# fnir_motherboard.net
KiCad netlist of a schematic drawn in EAGLE
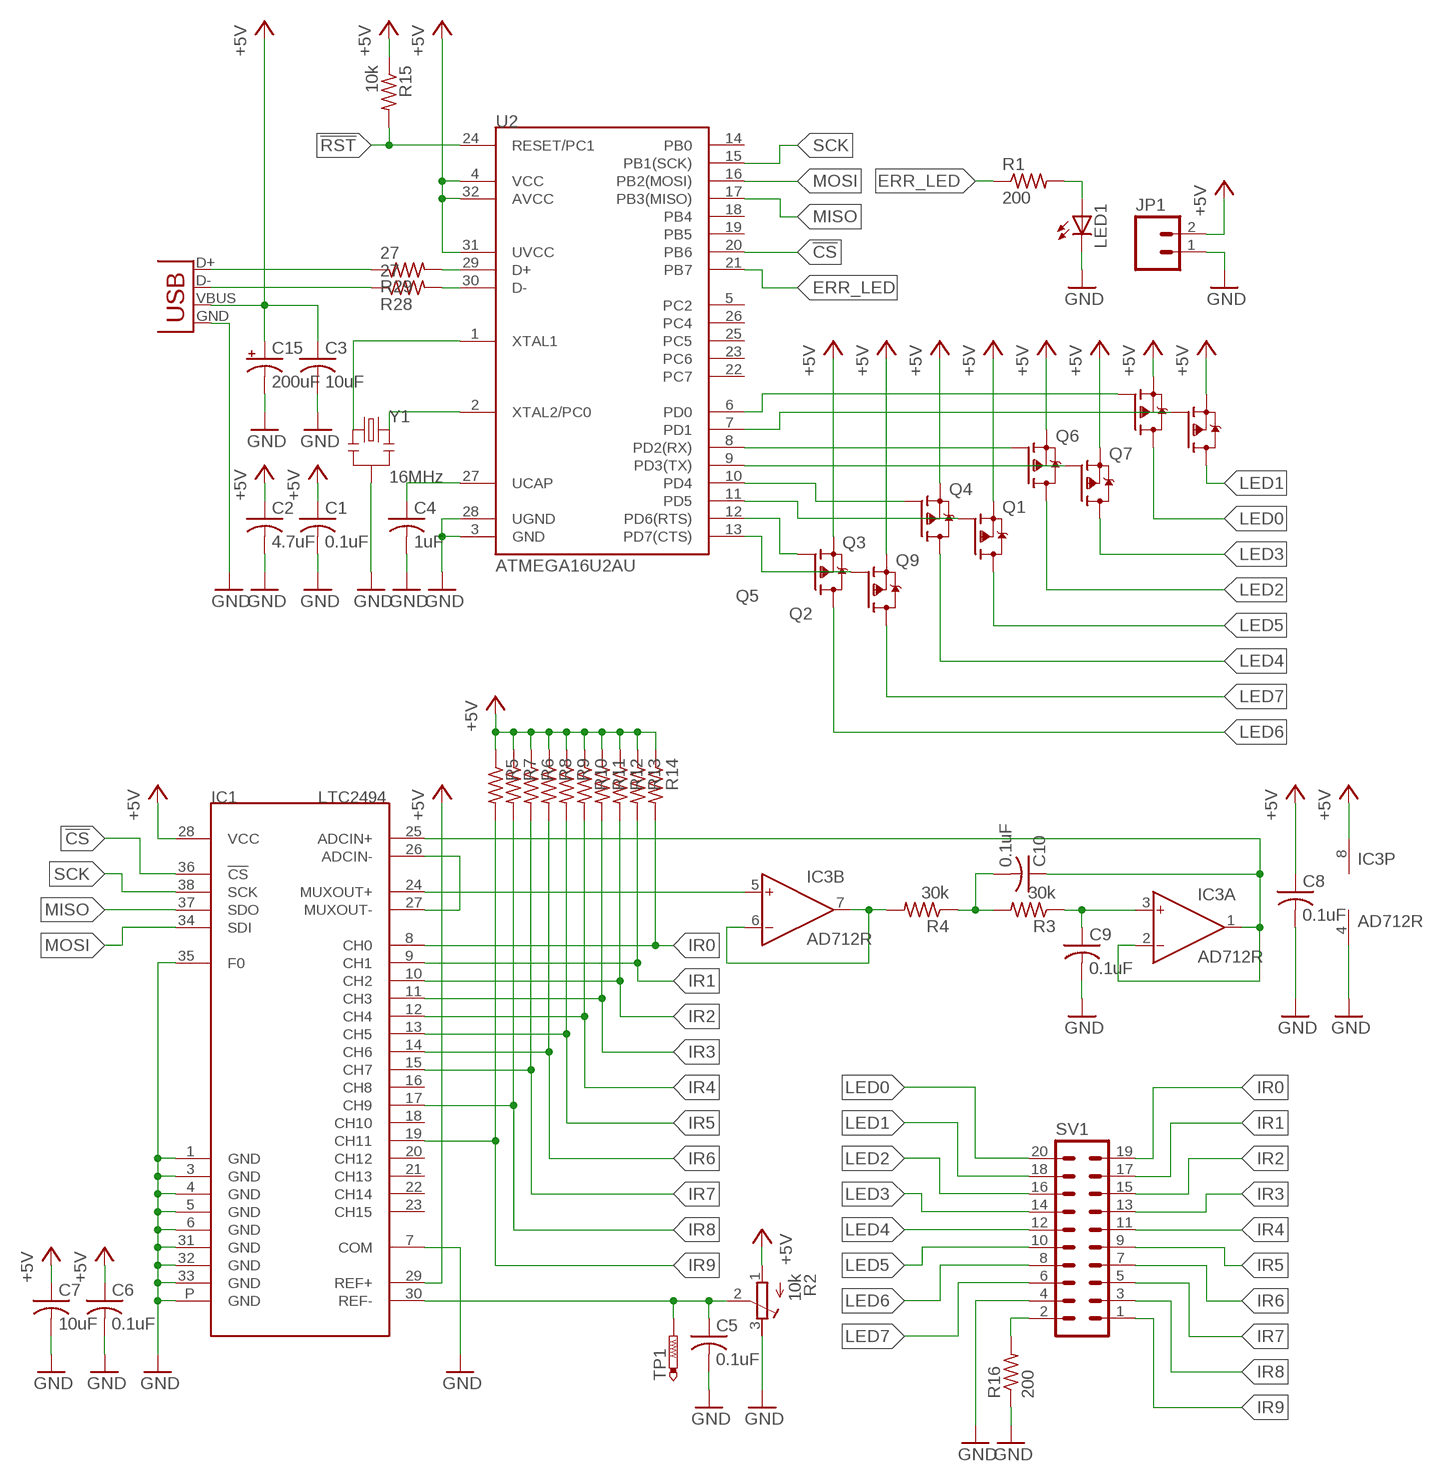
[diagram p0: schematic, sheet 1]

(export (version "E")
  (design (tool "Eeschema 10.0.6"))
  (components
    (comp (ref "C1")
      (value "0.1uF")
      (footprint "eagle-import:C1206")
      (libsource (lib "eagle-import") (part "C-USC1206"))
    )
    (comp (ref "C2")
      (value "4.7uF")
      (footprint "eagle-import:C1206")
      (libsource (lib "eagle-import") (part "C-USC1206"))
    )
    (comp (ref "C3")
      (value "10uF")
      (footprint "eagle-import:C1206")
      (libsource (lib "eagle-import") (part "C-USC1206"))
    )
    (comp (ref "C4")
      (value "1uF")
      (footprint "eagle-import:C1206")
      (libsource (lib "eagle-import") (part "C-USC1206"))
    )
    (comp (ref "C5")
      (value "0.1uF")
      (footprint "eagle-import:C1206")
      (libsource (lib "eagle-import") (part "C-USC1206"))
    )
    (comp (ref "C6")
      (value "0.1uF")
      (footprint "eagle-import:C1206")
      (libsource (lib "eagle-import") (part "C-USC1206"))
    )
    (comp (ref "C7")
      (value "10uF")
      (footprint "eagle-import:C1206")
      (libsource (lib "eagle-import") (part "C-USC1206"))
    )
    (comp (ref "C8")
      (value "0.1uF")
      (footprint "eagle-import:C1206")
      (libsource (lib "eagle-import") (part "C-USC1206"))
    )
    (comp (ref "C9")
      (value "0.1uF")
      (footprint "eagle-import:C1206")
      (libsource (lib "eagle-import") (part "C-USC1206"))
    )
    (comp (ref "C10")
      (value "0.1uF")
      (footprint "eagle-import:C1206")
      (libsource (lib "eagle-import") (part "C-USC1206"))
    )
    (comp (ref "C15")
      (value "200uF")
      (footprint "eagle-import:PANASONIC_D")
      (libsource (lib "eagle-import") (part "CPOL-USD"))
    )
    (comp (ref "IC1")
      (value "LTC2494")
      (footprint "eagle-import:QFN38-7X12")
      (libsource (lib "eagle-import") (part "LTC2494"))
    )
    (comp (ref "IC3")
      (value "AD712R")
      (footprint "eagle-import:SO8")
      (fields (field (name "MF") "ALTERA CORPORATION") (field (name "MPN") "AD712KRZ"))
      (libsource (lib "eagle-import") (part "AD712R"))
    )
    (comp (ref "JP1")
      (value "M02PTH")
      (footprint "eagle-import:1X02")
      (libsource (lib "eagle-import") (part "M02PTH"))
    )
    (comp (ref "LED1")
      (value "LEDCHIPLED_1206")
      (footprint "eagle-import:CHIPLED_1206")
      (libsource (lib "eagle-import") (part "LEDCHIPLED_1206"))
    )
    (comp (ref "Q1")
      (value "TRANSISTOR_FET_TSM2301CX")
      (footprint "eagle-import:SOT-23")
      (libsource (lib "eagle-import") (part "TRANSISTOR_FET_TSM2301CX"))
    )
    (comp (ref "Q2")
      (value "TRANSISTOR_FET_TSM2301CX")
      (footprint "eagle-import:SOT-23")
      (libsource (lib "eagle-import") (part "TRANSISTOR_FET_TSM2301CX"))
    )
    (comp (ref "Q3")
      (value "TRANSISTOR_FET_TSM2301CX")
      (footprint "eagle-import:SOT-23")
      (libsource (lib "eagle-import") (part "TRANSISTOR_FET_TSM2301CX"))
    )
    (comp (ref "Q4")
      (value "TRANSISTOR_FET_TSM2301CX")
      (footprint "eagle-import:SOT-23")
      (libsource (lib "eagle-import") (part "TRANSISTOR_FET_TSM2301CX"))
    )
    (comp (ref "Q5")
      (value "TRANSISTOR_FET_TSM2301CX")
      (footprint "eagle-import:SOT-23")
      (libsource (lib "eagle-import") (part "TRANSISTOR_FET_TSM2301CX"))
    )
    (comp (ref "Q6")
      (value "TRANSISTOR_FET_TSM2301CX")
      (footprint "eagle-import:SOT-23")
      (libsource (lib "eagle-import") (part "TRANSISTOR_FET_TSM2301CX"))
    )
    (comp (ref "Q7")
      (value "TRANSISTOR_FET_TSM2301CX")
      (footprint "eagle-import:SOT-23")
      (libsource (lib "eagle-import") (part "TRANSISTOR_FET_TSM2301CX"))
    )
    (comp (ref "Q9")
      (value "TRANSISTOR_FET_TSM2301CX")
      (footprint "eagle-import:SOT-23")
      (libsource (lib "eagle-import") (part "TRANSISTOR_FET_TSM2301CX"))
    )
    (comp (ref "R1")
      (value "200")
      (footprint "eagle-import:R1206")
      (libsource (lib "eagle-import") (part "R-US_R1206"))
    )
    (comp (ref "R2")
      (value "10k")
      (footprint "eagle-import:RTRIM3304W")
      (libsource (lib "eagle-import") (part "R-TRIMM3304W"))
    )
    (comp (ref "R3")
      (value "30k")
      (footprint "eagle-import:R1206")
      (libsource (lib "eagle-import") (part "R-US_R1206"))
    )
    (comp (ref "R4")
      (value "30k")
      (footprint "eagle-import:R1206")
      (libsource (lib "eagle-import") (part "R-US_R1206"))
    )
    (comp (ref "R5")
      (value "R-US_R1206")
      (footprint "eagle-import:R1206")
      (libsource (lib "eagle-import") (part "R-US_R1206"))
    )
    (comp (ref "R6")
      (value "R-US_R1206")
      (footprint "eagle-import:R1206")
      (libsource (lib "eagle-import") (part "R-US_R1206"))
    )
    (comp (ref "R7")
      (value "R-US_R1206")
      (footprint "eagle-import:R1206")
      (libsource (lib "eagle-import") (part "R-US_R1206"))
    )
    (comp (ref "R8")
      (value "R-US_R1206")
      (footprint "eagle-import:R1206")
      (libsource (lib "eagle-import") (part "R-US_R1206"))
    )
    (comp (ref "R9")
      (value "R-US_R1206")
      (footprint "eagle-import:R1206")
      (libsource (lib "eagle-import") (part "R-US_R1206"))
    )
    (comp (ref "R10")
      (value "R-US_R1206")
      (footprint "eagle-import:R1206")
      (libsource (lib "eagle-import") (part "R-US_R1206"))
    )
    (comp (ref "R11")
      (value "R-US_R1206")
      (footprint "eagle-import:R1206")
      (libsource (lib "eagle-import") (part "R-US_R1206"))
    )
    (comp (ref "R12")
      (value "R-US_R1206")
      (footprint "eagle-import:R1206")
      (libsource (lib "eagle-import") (part "R-US_R1206"))
    )
    (comp (ref "R13")
      (value "R-US_R1206")
      (footprint "eagle-import:R1206")
      (libsource (lib "eagle-import") (part "R-US_R1206"))
    )
    (comp (ref "R14")
      (value "R-US_R1206")
      (footprint "eagle-import:R1206")
      (libsource (lib "eagle-import") (part "R-US_R1206"))
    )
    (comp (ref "R15")
      (value "10k")
      (footprint "eagle-import:R1206")
      (libsource (lib "eagle-import") (part "R-US_R1206"))
    )
    (comp (ref "R16")
      (value "200")
      (footprint "eagle-import:R1206")
      (libsource (lib "eagle-import") (part "R-US_R1206"))
    )
    (comp (ref "R28")
      (value "27")
      (footprint "eagle-import:R1206")
      (libsource (lib "eagle-import") (part "R-US_R1206"))
    )
    (comp (ref "R29")
      (value "27")
      (footprint "eagle-import:R1206")
      (libsource (lib "eagle-import") (part "R-US_R1206"))
    )
    (comp (ref "SV1")
      (value "MA10-2")
      (footprint "eagle-import:MA10-2")
      (libsource (lib "eagle-import") (part "MA10-2"))
    )
    (comp (ref "TP1")
      (value "PTR1B1,27")
      (footprint "eagle-import:B1,27")
      (libsource (lib "eagle-import") (part "PTR1B1,27"))
    )
    (comp (ref "U2")
      (value "ATMEGA16U2AU")
      (footprint "eagle-import:TQFP32-08")
      (libsource (lib "eagle-import") (part "ATMEGA8U2AU"))
    )
    (comp (ref "X2")
      (value "USB-SMD-NS")
      (footprint "eagle-import:USB-MINIB-NOSTOP")
      (libsource (lib "eagle-import") (part "USB-SMD-NS"))
    )
    (comp (ref "Y1")
      (value "16MHz")
      (footprint "eagle-import:RESONATOR-SMD")
      (libsource (lib "eagle-import") (part "RESONATORSMD"))
    )
  )
  (nets
    (net (code "1") (name "+5V") (class "Default")
      (node (ref "C1") (pin "1") (pinfunction "1_1") (pintype "passive"))
      (node (ref "C15") (pin "+") (pinfunction "+_+") (pintype "passive"))
      (node (ref "C2") (pin "1") (pinfunction "1_1") (pintype "passive"))
      (node (ref "C3") (pin "1") (pinfunction "1_1") (pintype "passive"))
      (node (ref "C6") (pin "1") (pinfunction "1_1") (pintype "passive"))
      (node (ref "C7") (pin "1") (pinfunction "1_1") (pintype "passive"))
      (node (ref "C8") (pin "1") (pinfunction "1_1") (pintype "passive"))
      (node (ref "IC1") (pin "28") (pinfunction "VCC_28") (pintype "bidirectional"))
      (node (ref "IC1") (pin "29") (pinfunction "REF+_29") (pintype "bidirectional"))
      (node (ref "IC3") (pin "8") (pinfunction "V+_8") (pintype "power_in"))
      (node (ref "JP1") (pin "2") (pinfunction "2_2") (pintype "passive"))
      (node (ref "Q1") (pin "2") (pinfunction "S_2") (pintype "passive"))
      (node (ref "Q2") (pin "2") (pinfunction "S_2") (pintype "passive"))
      (node (ref "Q3") (pin "2") (pinfunction "S_2") (pintype "passive"))
      (node (ref "Q4") (pin "2") (pinfunction "S_2") (pintype "passive"))
      (node (ref "Q5") (pin "2") (pinfunction "S_2") (pintype "passive"))
      (node (ref "Q6") (pin "2") (pinfunction "S_2") (pintype "passive"))
      (node (ref "Q7") (pin "2") (pinfunction "S_2") (pintype "passive"))
      (node (ref "Q9") (pin "2") (pinfunction "S_2") (pintype "passive"))
      (node (ref "R10") (pin "1") (pinfunction "1_1") (pintype "passive"))
      (node (ref "R11") (pin "1") (pinfunction "1_1") (pintype "passive"))
      (node (ref "R12") (pin "1") (pinfunction "1_1") (pintype "passive"))
      (node (ref "R13") (pin "1") (pinfunction "1_1") (pintype "passive"))
      (node (ref "R14") (pin "1") (pinfunction "1_1") (pintype "passive"))
      (node (ref "R15") (pin "1") (pinfunction "1_1") (pintype "passive"))
      (node (ref "R2") (pin "1") (pinfunction "A_1") (pintype "passive"))
      (node (ref "R5") (pin "1") (pinfunction "1_1") (pintype "passive"))
      (node (ref "R6") (pin "1") (pinfunction "1_1") (pintype "passive"))
      (node (ref "R7") (pin "1") (pinfunction "1_1") (pintype "passive"))
      (node (ref "R8") (pin "1") (pinfunction "1_1") (pintype "passive"))
      (node (ref "R9") (pin "1") (pinfunction "1_1") (pintype "passive"))
      (node (ref "U2") (pin "31") (pinfunction "UVCC_31") (pintype "bidirectional"))
      (node (ref "U2") (pin "32") (pinfunction "AVCC_32") (pintype "bidirectional"))
      (node (ref "U2") (pin "4") (pinfunction "VCC_4") (pintype "bidirectional"))
      (node (ref "X2") (pin "VBUS") (pinfunction "VBUS_VBUS") (pintype "bidirectional"))
    )
    (net (code "2") (name "/~{CS}") (class "Default")
      (node (ref "IC1") (pin "36") (pinfunction "~{CS}_36") (pintype "bidirectional"))
      (node (ref "U2") (pin "20") (pinfunction "PB6_20") (pintype "bidirectional"))
    )
    (net (code "3") (name "/~{RST}") (class "Default")
      (node (ref "R15") (pin "2") (pinfunction "2_2") (pintype "passive"))
      (node (ref "U2") (pin "24") (pinfunction "RESET/PC1_24") (pintype "bidirectional"))
    )
    (net (code "4") (name "ERR_LED") (class "Default")
      (node (ref "R1") (pin "1") (pinfunction "1_1") (pintype "passive"))
      (node (ref "U2") (pin "21") (pinfunction "PB7_21") (pintype "bidirectional"))
    )
    (net (code "5") (name "GND") (class "Default")
      (node (ref "C1") (pin "2") (pinfunction "2_2") (pintype "passive"))
      (node (ref "C15") (pin "-") (pinfunction "-_-") (pintype "passive"))
      (node (ref "C2") (pin "2") (pinfunction "2_2") (pintype "passive"))
      (node (ref "C3") (pin "2") (pinfunction "2_2") (pintype "passive"))
      (node (ref "C4") (pin "2") (pinfunction "2_2") (pintype "passive"))
      (node (ref "C5") (pin "2") (pinfunction "2_2") (pintype "passive"))
      (node (ref "C6") (pin "2") (pinfunction "2_2") (pintype "passive"))
      (node (ref "C7") (pin "2") (pinfunction "2_2") (pintype "passive"))
      (node (ref "C8") (pin "2") (pinfunction "2_2") (pintype "passive"))
      (node (ref "C9") (pin "2") (pinfunction "2_2") (pintype "passive"))
      (node (ref "IC1") (pin "1") (pinfunction "GND_1") (pintype "bidirectional"))
      (node (ref "IC1") (pin "3") (pinfunction "GND_3") (pintype "bidirectional"))
      (node (ref "IC1") (pin "31") (pinfunction "GND_31") (pintype "bidirectional"))
      (node (ref "IC1") (pin "32") (pinfunction "GND_32") (pintype "bidirectional"))
      (node (ref "IC1") (pin "33") (pinfunction "GND_33") (pintype "bidirectional"))
      (node (ref "IC1") (pin "35") (pinfunction "F0_35") (pintype "bidirectional"))
      (node (ref "IC1") (pin "4") (pinfunction "GND_4") (pintype "bidirectional"))
      (node (ref "IC1") (pin "5") (pinfunction "GND_5") (pintype "bidirectional"))
      (node (ref "IC1") (pin "6") (pinfunction "GND_6") (pintype "bidirectional"))
      (node (ref "IC1") (pin "7") (pinfunction "COM_7") (pintype "bidirectional"))
      (node (ref "IC1") (pin "P") (pinfunction "GND_P") (pintype "bidirectional"))
      (node (ref "IC3") (pin "4") (pinfunction "V-_4") (pintype "power_in"))
      (node (ref "JP1") (pin "1") (pinfunction "1_1") (pintype "passive"))
      (node (ref "LED1") (pin "C") (pinfunction "C_C") (pintype "passive"))
      (node (ref "R16") (pin "1") (pinfunction "1_1") (pintype "passive"))
      (node (ref "R2") (pin "3") (pinfunction "E_3") (pintype "passive"))
      (node (ref "SV1") (pin "4") (pinfunction "4_4") (pintype "passive"))
      (node (ref "U2") (pin "28") (pinfunction "UGND_28") (pintype "bidirectional"))
      (node (ref "U2") (pin "3") (pinfunction "GND_3") (pintype "bidirectional"))
      (node (ref "X2") (pin "GND") (pinfunction "GND_GND") (pintype "bidirectional"))
      (node (ref "Y1") (pin "2") (pinfunction "2_2") (pintype "passive"))
    )
    (net (code "6") (name "IR0") (class "Default")
      (node (ref "IC1") (pin "8") (pinfunction "CH0_8") (pintype "bidirectional"))
      (node (ref "R14") (pin "2") (pinfunction "2_2") (pintype "passive"))
      (node (ref "SV1") (pin "19") (pinfunction "19_19") (pintype "passive"))
    )
    (net (code "7") (name "IR1") (class "Default")
      (node (ref "IC1") (pin "9") (pinfunction "CH1_9") (pintype "bidirectional"))
      (node (ref "R13") (pin "2") (pinfunction "2_2") (pintype "passive"))
      (node (ref "SV1") (pin "17") (pinfunction "17_17") (pintype "passive"))
    )
    (net (code "8") (name "IR2") (class "Default")
      (node (ref "IC1") (pin "10") (pinfunction "CH2_10") (pintype "bidirectional"))
      (node (ref "R12") (pin "2") (pinfunction "2_2") (pintype "passive"))
      (node (ref "SV1") (pin "15") (pinfunction "15_15") (pintype "passive"))
    )
    (net (code "9") (name "IR3") (class "Default")
      (node (ref "IC1") (pin "11") (pinfunction "CH3_11") (pintype "bidirectional"))
      (node (ref "R11") (pin "2") (pinfunction "2_2") (pintype "passive"))
      (node (ref "SV1") (pin "13") (pinfunction "13_13") (pintype "passive"))
    )
    (net (code "10") (name "IR4") (class "Default")
      (node (ref "IC1") (pin "12") (pinfunction "CH4_12") (pintype "bidirectional"))
      (node (ref "R10") (pin "2") (pinfunction "2_2") (pintype "passive"))
      (node (ref "SV1") (pin "11") (pinfunction "11_11") (pintype "passive"))
    )
    (net (code "11") (name "IR5") (class "Default")
      (node (ref "IC1") (pin "13") (pinfunction "CH5_13") (pintype "bidirectional"))
      (node (ref "R9") (pin "2") (pinfunction "2_2") (pintype "passive"))
      (node (ref "SV1") (pin "9") (pinfunction "9_9") (pintype "passive"))
    )
    (net (code "12") (name "IR6") (class "Default")
      (node (ref "IC1") (pin "14") (pinfunction "CH6_14") (pintype "bidirectional"))
      (node (ref "R8") (pin "2") (pinfunction "2_2") (pintype "passive"))
      (node (ref "SV1") (pin "7") (pinfunction "7_7") (pintype "passive"))
    )
    (net (code "13") (name "IR7") (class "Default")
      (node (ref "IC1") (pin "15") (pinfunction "CH7_15") (pintype "bidirectional"))
      (node (ref "R6") (pin "2") (pinfunction "2_2") (pintype "passive"))
      (node (ref "SV1") (pin "5") (pinfunction "5_5") (pintype "passive"))
    )
    (net (code "14") (name "IR8") (class "Default")
      (node (ref "IC1") (pin "17") (pinfunction "CH9_17") (pintype "bidirectional"))
      (node (ref "R7") (pin "2") (pinfunction "2_2") (pintype "passive"))
      (node (ref "SV1") (pin "3") (pinfunction "3_3") (pintype "passive"))
    )
    (net (code "15") (name "IR9") (class "Default")
      (node (ref "IC1") (pin "19") (pinfunction "CH11_19") (pintype "bidirectional"))
      (node (ref "R5") (pin "2") (pinfunction "2_2") (pintype "passive"))
      (node (ref "SV1") (pin "1") (pinfunction "1_1") (pintype "passive"))
    )
    (net (code "16") (name "LED0") (class "Default")
      (node (ref "Q6") (pin "3") (pinfunction "D_3") (pintype "passive"))
      (node (ref "SV1") (pin "20") (pinfunction "20_20") (pintype "passive"))
    )
    (net (code "17") (name "LED1") (class "Default")
      (node (ref "Q7") (pin "3") (pinfunction "D_3") (pintype "passive"))
      (node (ref "SV1") (pin "18") (pinfunction "18_18") (pintype "passive"))
    )
    (net (code "18") (name "LED2") (class "Default")
      (node (ref "Q4") (pin "3") (pinfunction "D_3") (pintype "passive"))
      (node (ref "SV1") (pin "16") (pinfunction "16_16") (pintype "passive"))
    )
    (net (code "19") (name "LED3") (class "Default")
      (node (ref "Q1") (pin "3") (pinfunction "D_3") (pintype "passive"))
      (node (ref "SV1") (pin "14") (pinfunction "14_14") (pintype "passive"))
    )
    (net (code "20") (name "LED4") (class "Default")
      (node (ref "Q3") (pin "3") (pinfunction "D_3") (pintype "passive"))
      (node (ref "SV1") (pin "12") (pinfunction "12_12") (pintype "passive"))
    )
    (net (code "21") (name "LED5") (class "Default")
      (node (ref "Q9") (pin "3") (pinfunction "D_3") (pintype "passive"))
      (node (ref "SV1") (pin "10") (pinfunction "10_10") (pintype "passive"))
    )
    (net (code "22") (name "LED6") (class "Default")
      (node (ref "Q5") (pin "3") (pinfunction "D_3") (pintype "passive"))
      (node (ref "SV1") (pin "8") (pinfunction "8_8") (pintype "passive"))
    )
    (net (code "23") (name "LED7") (class "Default")
      (node (ref "Q2") (pin "3") (pinfunction "D_3") (pintype "passive"))
      (node (ref "SV1") (pin "6") (pinfunction "6_6") (pintype "passive"))
    )
    (net (code "24") (name "MISO") (class "Default")
      (node (ref "IC1") (pin "37") (pinfunction "SDO_37") (pintype "bidirectional"))
      (node (ref "U2") (pin "17") (pinfunction "PB3(MISO)_17") (pintype "bidirectional"))
    )
    (net (code "25") (name "MOSI") (class "Default")
      (node (ref "IC1") (pin "34") (pinfunction "SDI_34") (pintype "bidirectional"))
      (node (ref "U2") (pin "16") (pinfunction "PB2(MOSI)_16") (pintype "bidirectional"))
    )
    (net (code "26") (name "Net-(C10-Pad2)") (class "Default")
      (node (ref "C10") (pin "2") (pinfunction "2_2") (pintype "passive"))
      (node (ref "R3") (pin "2") (pinfunction "2_2") (pintype "passive"))
      (node (ref "R4") (pin "1") (pinfunction "1_1") (pintype "passive"))
    )
    (net (code "27") (name "Net-(IC1-ADCIN+)") (class "Default")
      (node (ref "C10") (pin "1") (pinfunction "1_1") (pintype "passive"))
      (node (ref "IC1") (pin "25") (pinfunction "ADCIN+_25") (pintype "bidirectional"))
      (node (ref "IC3") (pin "1") (pinfunction "OUT_1") (pintype "output"))
      (node (ref "IC3") (pin "2") (pinfunction "IN-_2") (pintype "input"))
    )
    (net (code "28") (name "Net-(IC1-ADCIN-)") (class "Default")
      (node (ref "IC1") (pin "26") (pinfunction "ADCIN-_26") (pintype "bidirectional"))
      (node (ref "IC1") (pin "27") (pinfunction "MUXOUT-_27") (pintype "bidirectional"))
    )
    (net (code "29") (name "Net-(IC1-MUXOUT+)") (class "Default")
      (node (ref "IC1") (pin "24") (pinfunction "MUXOUT+_24") (pintype "bidirectional"))
      (node (ref "IC3") (pin "5") (pinfunction "IN+_5") (pintype "input"))
    )
    (net (code "30") (name "Net-(IC1-REF-)") (class "Default")
      (node (ref "C5") (pin "1") (pinfunction "1_1") (pintype "passive"))
      (node (ref "IC1") (pin "30") (pinfunction "REF-_30") (pintype "bidirectional"))
      (node (ref "R2") (pin "2") (pinfunction "S_2") (pintype "passive"))
      (node (ref "TP1") (pin "TP") (pinfunction "TP_TP") (pintype "input"))
    )
    (net (code "31") (name "Net-(IC3A-IN+)") (class "Default")
      (node (ref "C9") (pin "1") (pinfunction "1_1") (pintype "passive"))
      (node (ref "IC3") (pin "3") (pinfunction "IN+_3") (pintype "input"))
      (node (ref "R3") (pin "1") (pinfunction "1_1") (pintype "passive"))
    )
    (net (code "32") (name "Net-(IC3B-IN-)") (class "Default")
      (node (ref "IC3") (pin "6") (pinfunction "IN-_6") (pintype "input"))
      (node (ref "IC3") (pin "7") (pinfunction "OUT_7") (pintype "output"))
      (node (ref "R4") (pin "2") (pinfunction "2_2") (pintype "passive"))
    )
    (net (code "33") (name "Net-(LED1-PadA)") (class "Default")
      (node (ref "LED1") (pin "A") (pinfunction "A_A") (pintype "passive"))
      (node (ref "R1") (pin "2") (pinfunction "2_2") (pintype "passive"))
    )
    (net (code "34") (name "Net-(Q1-G)") (class "Default")
      (node (ref "Q1") (pin "1") (pinfunction "G_1") (pintype "passive"))
      (node (ref "U2") (pin "9") (pinfunction "PD3(TX)_9") (pintype "bidirectional"))
    )
    (net (code "35") (name "Net-(Q2-G)") (class "Default")
      (node (ref "Q2") (pin "1") (pinfunction "G_1") (pintype "passive"))
      (node (ref "U2") (pin "13") (pinfunction "PD7(CTS)_13") (pintype "bidirectional"))
    )
    (net (code "36") (name "Net-(Q3-G)") (class "Default")
      (node (ref "Q3") (pin "1") (pinfunction "G_1") (pintype "passive"))
      (node (ref "U2") (pin "10") (pinfunction "PD4_10") (pintype "bidirectional"))
    )
    (net (code "37") (name "Net-(Q4-G)") (class "Default")
      (node (ref "Q4") (pin "1") (pinfunction "G_1") (pintype "passive"))
      (node (ref "U2") (pin "8") (pinfunction "PD2(RX)_8") (pintype "bidirectional"))
    )
    (net (code "38") (name "Net-(Q5-G)") (class "Default")
      (node (ref "Q5") (pin "1") (pinfunction "G_1") (pintype "passive"))
      (node (ref "U2") (pin "12") (pinfunction "PD6(RTS)_12") (pintype "bidirectional"))
    )
    (net (code "39") (name "Net-(Q6-G)") (class "Default")
      (node (ref "Q6") (pin "1") (pinfunction "G_1") (pintype "passive"))
      (node (ref "U2") (pin "6") (pinfunction "PD0_6") (pintype "bidirectional"))
    )
    (net (code "40") (name "Net-(Q7-G)") (class "Default")
      (node (ref "Q7") (pin "1") (pinfunction "G_1") (pintype "passive"))
      (node (ref "U2") (pin "7") (pinfunction "PD1_7") (pintype "bidirectional"))
    )
    (net (code "41") (name "Net-(Q9-G)") (class "Default")
      (node (ref "Q9") (pin "1") (pinfunction "G_1") (pintype "passive"))
      (node (ref "U2") (pin "11") (pinfunction "PD5_11") (pintype "bidirectional"))
    )
    (net (code "42") (name "Net-(R16-Pad2)") (class "Default")
      (node (ref "R16") (pin "2") (pinfunction "2_2") (pintype "passive"))
      (node (ref "SV1") (pin "2") (pinfunction "2_2") (pintype "passive"))
    )
    (net (code "43") (name "Net-(R28-Pad1)") (class "Default")
      (node (ref "R28") (pin "1") (pinfunction "1_1") (pintype "passive"))
      (node (ref "X2") (pin "D-") (pinfunction "D-_D-") (pintype "bidirectional"))
    )
    (net (code "44") (name "Net-(R29-Pad1)") (class "Default")
      (node (ref "R29") (pin "1") (pinfunction "1_1") (pintype "passive"))
      (node (ref "X2") (pin "D+") (pinfunction "D+_D+") (pintype "bidirectional"))
    )
    (net (code "45") (name "Net-(U2-D+)") (class "Default")
      (node (ref "R29") (pin "2") (pinfunction "2_2") (pintype "passive"))
      (node (ref "U2") (pin "29") (pinfunction "D+_29") (pintype "bidirectional"))
    )
    (net (code "46") (name "Net-(U2-D-)") (class "Default")
      (node (ref "R28") (pin "2") (pinfunction "2_2") (pintype "passive"))
      (node (ref "U2") (pin "30") (pinfunction "D-_30") (pintype "bidirectional"))
    )
    (net (code "47") (name "Net-(U2-UCAP)") (class "Default")
      (node (ref "C4") (pin "1") (pinfunction "1_1") (pintype "passive"))
      (node (ref "U2") (pin "27") (pinfunction "UCAP_27") (pintype "bidirectional"))
    )
    (net (code "48") (name "Net-(U2-XTAL1)") (class "Default")
      (node (ref "U2") (pin "1") (pinfunction "XTAL1_1") (pintype "bidirectional"))
      (node (ref "Y1") (pin "1") (pinfunction "1_1") (pintype "passive"))
    )
    (net (code "49") (name "Net-(U2-XTAL2{slash}PC0)") (class "Default")
      (node (ref "U2") (pin "2") (pinfunction "XTAL2/PC0_2") (pintype "bidirectional"))
      (node (ref "Y1") (pin "3") (pinfunction "3_3") (pintype "passive"))
    )
    (net (code "50") (name "SCK") (class "Default")
      (node (ref "IC1") (pin "38") (pinfunction "SCK_38") (pintype "bidirectional"))
      (node (ref "U2") (pin "15") (pinfunction "PB1(SCK)_15") (pintype "bidirectional"))
    )
    (net (code "51") (name "unconnected-(IC1-CH8-Pad16)") (class "Default")
      (node (ref "IC1") (pin "16") (pinfunction "CH8_16") (pintype "bidirectional"))
    )
    (net (code "52") (name "unconnected-(IC1-CH10-Pad18)") (class "Default")
      (node (ref "IC1") (pin "18") (pinfunction "CH10_18") (pintype "bidirectional"))
    )
    (net (code "53") (name "unconnected-(IC1-CH12-Pad20)") (class "Default")
      (node (ref "IC1") (pin "20") (pinfunction "CH12_20") (pintype "bidirectional"))
    )
    (net (code "54") (name "unconnected-(IC1-CH13-Pad21)") (class "Default")
      (node (ref "IC1") (pin "21") (pinfunction "CH13_21") (pintype "bidirectional"))
    )
    (net (code "55") (name "unconnected-(IC1-CH14-Pad22)") (class "Default")
      (node (ref "IC1") (pin "22") (pinfunction "CH14_22") (pintype "bidirectional"))
    )
    (net (code "56") (name "unconnected-(IC1-CH15-Pad23)") (class "Default")
      (node (ref "IC1") (pin "23") (pinfunction "CH15_23") (pintype "bidirectional"))
    )
    (net (code "57") (name "unconnected-(U2-PB0-Pad14)") (class "Default")
      (node (ref "U2") (pin "14") (pinfunction "PB0_14") (pintype "bidirectional"))
    )
    (net (code "58") (name "unconnected-(U2-PB4-Pad18)") (class "Default")
      (node (ref "U2") (pin "18") (pinfunction "PB4_18") (pintype "bidirectional"))
    )
    (net (code "59") (name "unconnected-(U2-PB5-Pad19)") (class "Default")
      (node (ref "U2") (pin "19") (pinfunction "PB5_19") (pintype "bidirectional"))
    )
    (net (code "60") (name "unconnected-(U2-PC2-Pad5)") (class "Default")
      (node (ref "U2") (pin "5") (pinfunction "PC2_5") (pintype "bidirectional"))
    )
    (net (code "61") (name "unconnected-(U2-PC4-Pad26)") (class "Default")
      (node (ref "U2") (pin "26") (pinfunction "PC4_26") (pintype "bidirectional"))
    )
    (net (code "62") (name "unconnected-(U2-PC5-Pad25)") (class "Default")
      (node (ref "U2") (pin "25") (pinfunction "PC5_25") (pintype "bidirectional"))
    )
    (net (code "63") (name "unconnected-(U2-PC6-Pad23)") (class "Default")
      (node (ref "U2") (pin "23") (pinfunction "PC6_23") (pintype "bidirectional"))
    )
    (net (code "64") (name "unconnected-(U2-PC7-Pad22)") (class "Default")
      (node (ref "U2") (pin "22") (pinfunction "PC7_22") (pintype "bidirectional"))
    )
  )
)
